# Fyre-BASIC-BOTtom.net
KiCad netlist of a schematic drawn in EAGLE
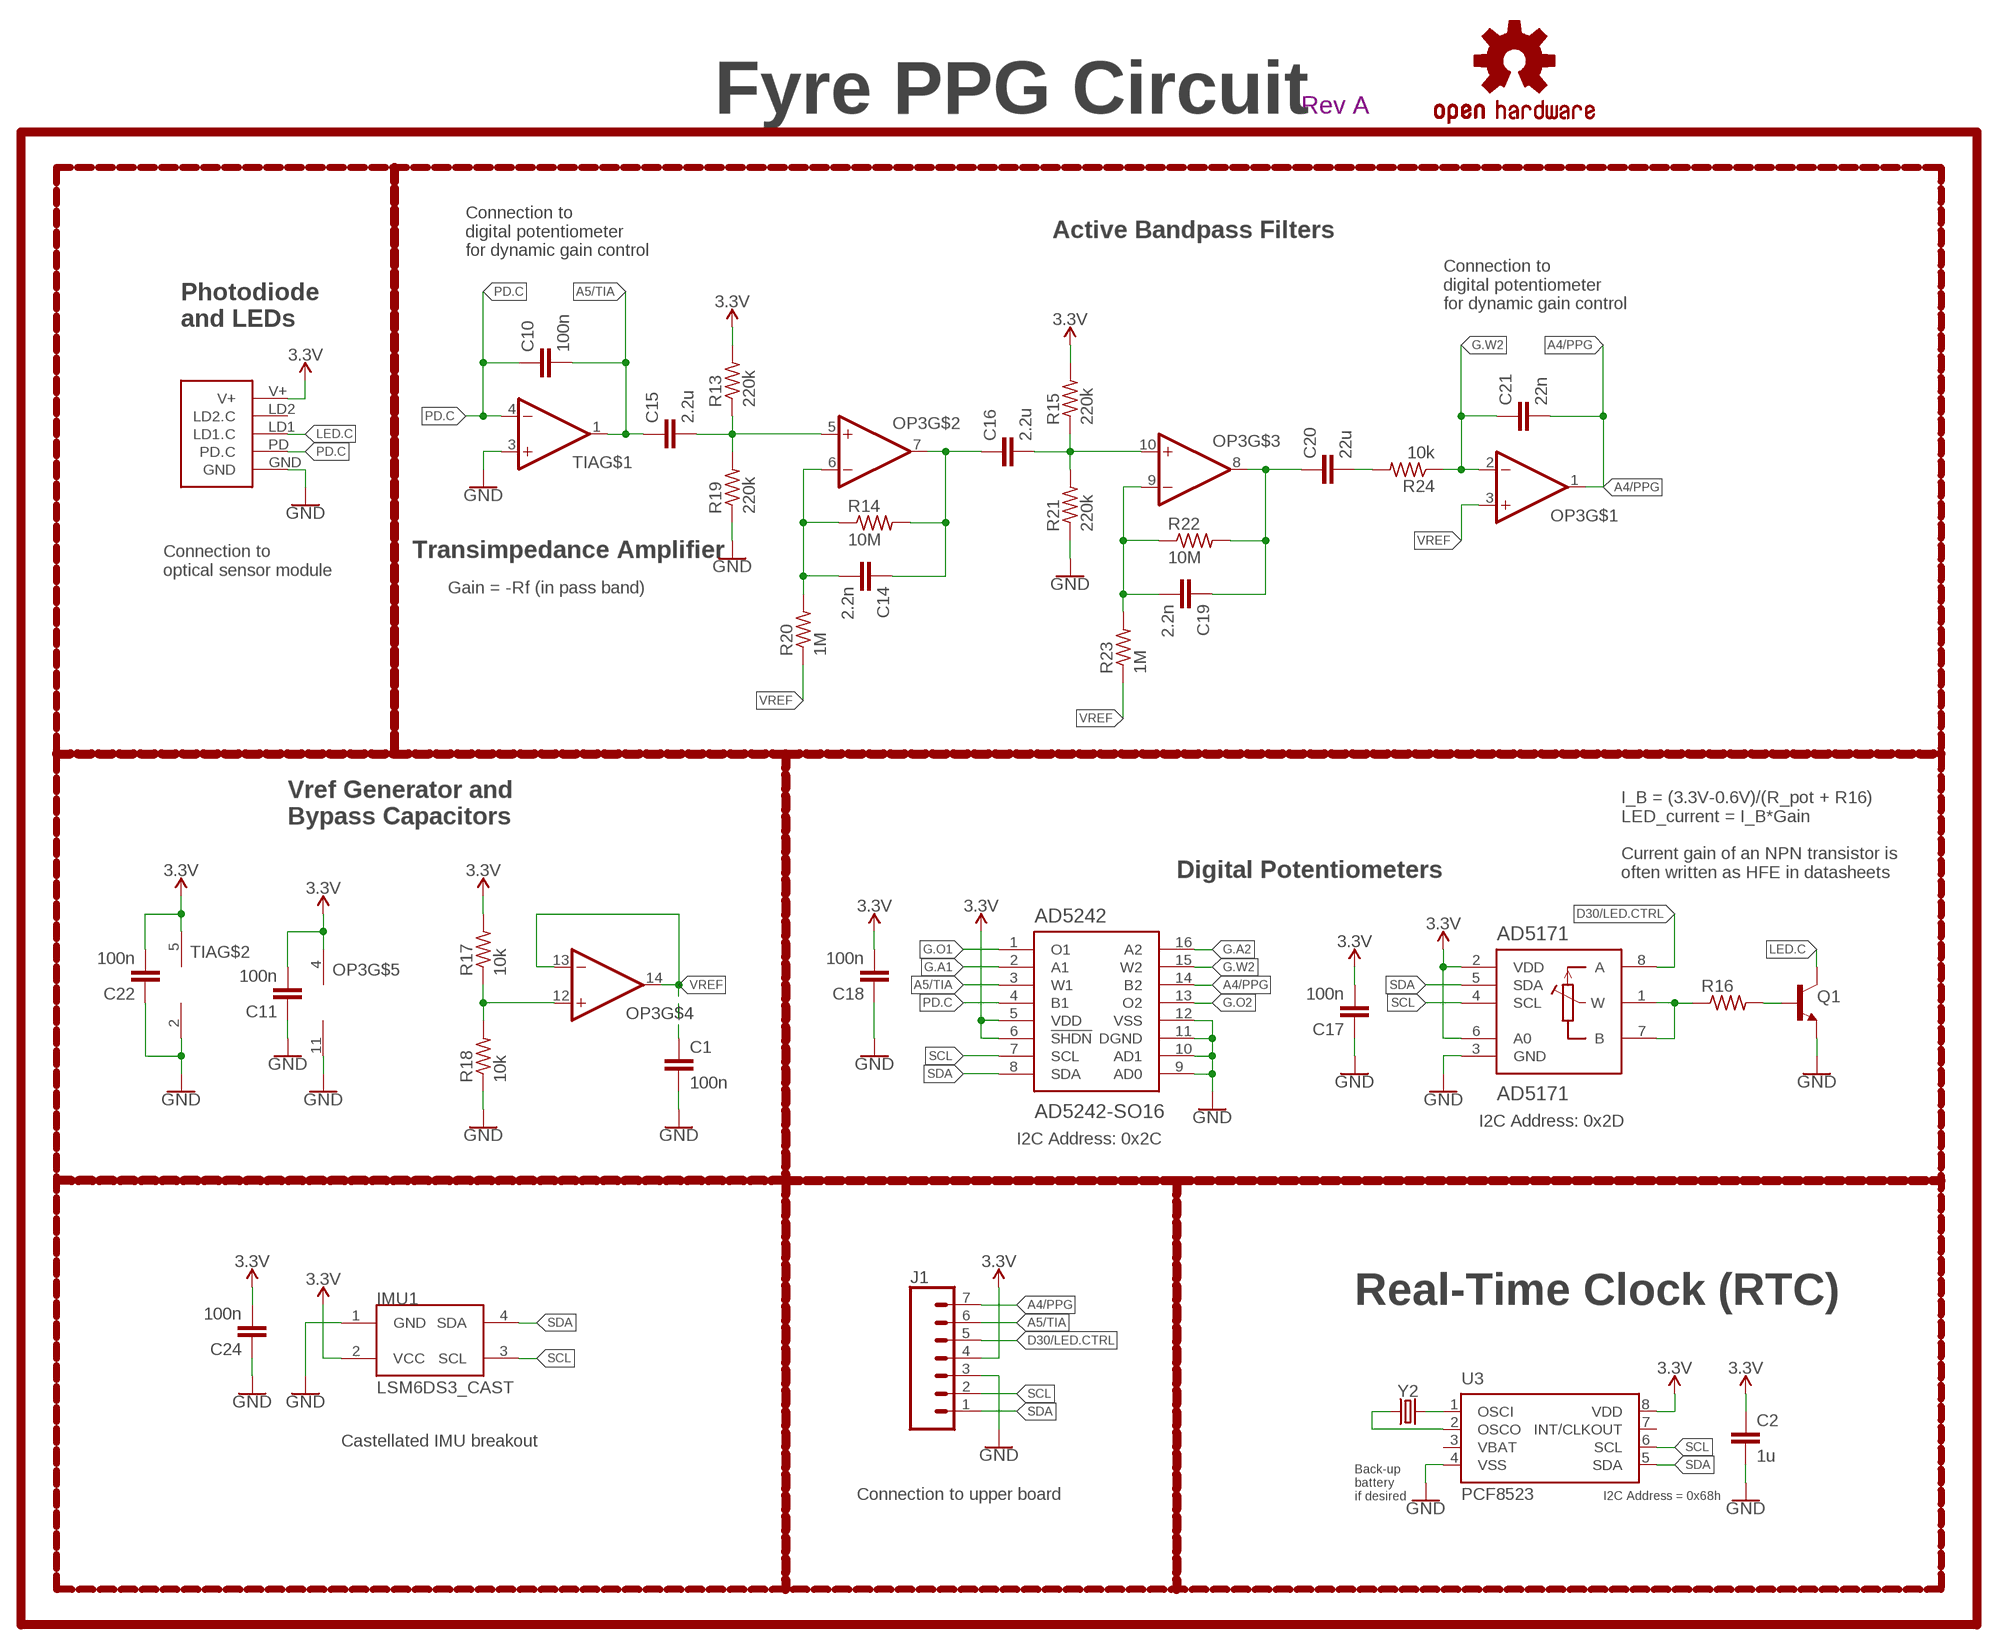
[diagram p0: schematic, sheet 1]

(export (version "E")
  (design (tool "Eeschema 10.0.6"))
  (components
    (comp (ref "AD5171")
      (value "AD5171")
      (footprint "eagle-import:SOT-23-8")
      (libsource (lib "eagle-import") (part "AD5171"))
    )
    (comp (ref "AD5242")
      (value "AD5242-SO16")
      (footprint "eagle-import:SO16")
      (libsource (lib "eagle-import") (part "AD5242-SO16"))
    )
    (comp (ref "C1")
      (value "100n")
      (footprint "eagle-import:C0603")
      (libsource (lib "eagle-import") (part "CAPACITOR0603"))
    )
    (comp (ref "C2")
      (value "1u")
      (footprint "eagle-import:C0603")
      (libsource (lib "eagle-import") (part "CAPACITOR0603"))
    )
    (comp (ref "C10")
      (value "100n")
      (footprint "eagle-import:C0603")
      (libsource (lib "eagle-import") (part "CAPACITOR0603"))
    )
    (comp (ref "C11")
      (value "100n")
      (footprint "eagle-import:C0603")
      (libsource (lib "eagle-import") (part "CAPACITOR0603"))
    )
    (comp (ref "C14")
      (value "2.2n")
      (footprint "eagle-import:C0603")
      (libsource (lib "eagle-import") (part "CAPACITOR0603"))
    )
    (comp (ref "C15")
      (value "2.2u")
      (footprint "eagle-import:C0603")
      (libsource (lib "eagle-import") (part "CAPACITOR0603"))
    )
    (comp (ref "C16")
      (value "2.2u")
      (footprint "eagle-import:C0603")
      (libsource (lib "eagle-import") (part "CAPACITOR0603"))
    )
    (comp (ref "C17")
      (value "100n")
      (footprint "eagle-import:C0603")
      (libsource (lib "eagle-import") (part "CAPACITOR0603"))
    )
    (comp (ref "C18")
      (value "100n")
      (footprint "eagle-import:C0603")
      (libsource (lib "eagle-import") (part "CAPACITOR0603"))
    )
    (comp (ref "C19")
      (value "2.2n")
      (footprint "eagle-import:C0603")
      (libsource (lib "eagle-import") (part "CAPACITOR0603"))
    )
    (comp (ref "C20")
      (value "22u")
      (footprint "eagle-import:C0603")
      (libsource (lib "eagle-import") (part "CAPACITOR0603"))
    )
    (comp (ref "C21")
      (value "22n")
      (footprint "eagle-import:C0603")
      (libsource (lib "eagle-import") (part "CAPACITOR0603"))
    )
    (comp (ref "C22")
      (value "100n")
      (footprint "eagle-import:C0603")
      (libsource (lib "eagle-import") (part "CAPACITOR0603"))
    )
    (comp (ref "C24")
      (value "100n")
      (footprint "eagle-import:C0603")
      (libsource (lib "eagle-import") (part "CAPACITOR0603"))
    )
    (comp (ref "IMU1")
      (value "LSM6DS3_CAST")
      (footprint "eagle-import:LSM6DS3_CAST")
      (libsource (lib "eagle-import") (part "LSM6DS3_CAST"))
    )
    (comp (ref "J1")
      (value "CONN_07-1.27MM")
      (footprint "eagle-import:1X07_1.27MM")
      (libsource (lib "eagle-import") (part "CONN_07-1.27MM"))
    )
    (comp (ref "LOGO1")
      (value "REVISION.A")
      (footprint "eagle-import:REV.A")
      (libsource (lib "eagle-import") (part "REVISION.A"))
    )
    (comp (ref "LOGO2")
      (value "OSHW-LOGOS")
      (footprint "eagle-import:OSHW-LOGO-S")
      (libsource (lib "eagle-import") (part "OSHW-LOGOS"))
    )
    (comp (ref "OP3")
      (value "OP-QUAD-SO14")
      (footprint "eagle-import:SO14")
      (libsource (lib "eagle-import") (part "OP-QUAD-SO14"))
    )
    (comp (ref "Q1")
      (value "NPN-GENERIC")
      (footprint "eagle-import:SOT23-3")
      (libsource (lib "eagle-import") (part "NPN-GENERIC"))
    )
    (comp (ref "R13")
      (value "220k")
      (footprint "eagle-import:R0603")
      (libsource (lib "eagle-import") (part "RESISTOR0603"))
    )
    (comp (ref "R14")
      (value "10M")
      (footprint "eagle-import:R0603")
      (libsource (lib "eagle-import") (part "RESISTOR0603"))
    )
    (comp (ref "R15")
      (value "220k")
      (footprint "eagle-import:R0603")
      (libsource (lib "eagle-import") (part "RESISTOR0603"))
    )
    (comp (ref "R16")
      (value "RESISTOR0603")
      (footprint "eagle-import:R0603")
      (libsource (lib "eagle-import") (part "RESISTOR0603"))
    )
    (comp (ref "R17")
      (value "10k")
      (footprint "eagle-import:R0402")
      (libsource (lib "eagle-import") (part "RESISTOR0402"))
    )
    (comp (ref "R18")
      (value "10k")
      (footprint "eagle-import:R0402")
      (libsource (lib "eagle-import") (part "RESISTOR0402"))
    )
    (comp (ref "R19")
      (value "220k")
      (footprint "eagle-import:R0603")
      (libsource (lib "eagle-import") (part "RESISTOR0603"))
    )
    (comp (ref "R20")
      (value "1M")
      (footprint "eagle-import:R0603")
      (libsource (lib "eagle-import") (part "RESISTOR0603"))
    )
    (comp (ref "R21")
      (value "220k")
      (footprint "eagle-import:R0603")
      (libsource (lib "eagle-import") (part "RESISTOR0603"))
    )
    (comp (ref "R22")
      (value "10M")
      (footprint "eagle-import:R0603")
      (libsource (lib "eagle-import") (part "RESISTOR0603"))
    )
    (comp (ref "R23")
      (value "1M")
      (footprint "eagle-import:R0603")
      (libsource (lib "eagle-import") (part "RESISTOR0603"))
    )
    (comp (ref "R24")
      (value "10k")
      (footprint "eagle-import:R0603")
      (libsource (lib "eagle-import") (part "RESISTOR0603"))
    )
    (comp (ref "TIA")
      (value "OP-SINGLEOT")
      (footprint "eagle-import:SOT23-5")
      (libsource (lib "eagle-import") (part "OP-SINGLEOT"))
    )
    (comp (ref "U$3")
      (value "PPG.MODULE.2")
      (footprint "eagle-import:PPG.MODULE.2")
      (libsource (lib "eagle-import") (part "PPG.MODULE.2"))
    )
    (comp (ref "U3")
      (value "PCF8523")
      (footprint "eagle-import:SO8")
      (fields
        (field (name "DIGIKEY") "568-5306-1-ND")
        (field (name "I2C_ADDRESS") "0x68h")
        (field (name "MFN") "PCF8523T/1,118")
        (field (name "MFN_MANUFACTURER") "NXP USA Inc.")
      )
      (libsource (lib "eagle-import") (part "PCF8523"))
    )
    (comp (ref "Y2")
      (value "32.7680kHz")
      (footprint "eagle-import:2-SMD.NOLEAD.2.0MMTO1.2MM")
      (fields (field (name "FREQ") "32.7680KHZ"))
      (libsource (lib "eagle-import") (part "CRYSTALECS-.327-12.5-12-C-TR"))
    )
  )
  (nets
    (net (code "1") (name "/VBAT") (class "Default")
      (node (ref "U3") (pin "3") (pinfunction "VBAT_3") (pintype "power_in"))
    )
    (net (code "2") (name "3.3V") (class "Default")
      (node (ref "AD5171") (pin "2") (pinfunction "VDD_2") (pintype "bidirectional"))
      (node (ref "AD5171") (pin "6") (pinfunction "A0_6") (pintype "bidirectional"))
      (node (ref "AD5242") (pin "5") (pinfunction "VDD_5") (pintype "bidirectional"))
      (node (ref "AD5242") (pin "6") (pinfunction "~{SHDN}_6") (pintype "bidirectional"))
      (node (ref "C11") (pin "2") (pinfunction "2_2") (pintype "passive"))
      (node (ref "C17") (pin "2") (pinfunction "2_2") (pintype "passive"))
      (node (ref "C18") (pin "2") (pinfunction "2_2") (pintype "passive"))
      (node (ref "C2") (pin "1") (pinfunction "1_1") (pintype "passive"))
      (node (ref "C22") (pin "2") (pinfunction "2_2") (pintype "passive"))
      (node (ref "C24") (pin "2") (pinfunction "2_2") (pintype "passive"))
      (node (ref "IMU1") (pin "2") (pinfunction "VCC_2") (pintype "bidirectional"))
      (node (ref "J1") (pin "4") (pinfunction "4_4") (pintype "passive"))
      (node (ref "OP3") (pin "4") (pinfunction "V+_4") (pintype "power_in"))
      (node (ref "R13") (pin "2") (pinfunction "2_2") (pintype "passive"))
      (node (ref "R15") (pin "2") (pinfunction "2_2") (pintype "passive"))
      (node (ref "R17") (pin "2") (pinfunction "2_2") (pintype "passive"))
      (node (ref "TIA") (pin "5") (pinfunction "V+_5") (pintype "power_in"))
      (node (ref "U$3") (pin "V+") (pinfunction "V+_V+") (pintype "bidirectional"))
      (node (ref "U3") (pin "8") (pinfunction "VDD_8") (pintype "power_in"))
    )
    (net (code "3") (name "A4{slash}PPG") (class "Default")
      (node (ref "AD5242") (pin "14") (pinfunction "B2_14") (pintype "bidirectional"))
      (node (ref "C21") (pin "2") (pinfunction "2_2") (pintype "passive"))
      (node (ref "J1") (pin "7") (pinfunction "7_7") (pintype "passive"))
      (node (ref "OP3") (pin "1") (pinfunction "OUT_1") (pintype "output"))
    )
    (net (code "4") (name "A5{slash}TIA") (class "Default")
      (node (ref "AD5242") (pin "3") (pinfunction "W1_3") (pintype "bidirectional"))
      (node (ref "C10") (pin "2") (pinfunction "2_2") (pintype "passive"))
      (node (ref "C15") (pin "1") (pinfunction "1_1") (pintype "passive"))
      (node (ref "J1") (pin "6") (pinfunction "6_6") (pintype "passive"))
      (node (ref "TIA") (pin "1") (pinfunction "OUT_1") (pintype "output"))
    )
    (net (code "5") (name "D30{slash}LED.CTRL") (class "Default")
      (node (ref "AD5171") (pin "8") (pinfunction "A_8") (pintype "bidirectional"))
      (node (ref "J1") (pin "5") (pinfunction "5_5") (pintype "passive"))
    )
    (net (code "6") (name "G.A1") (class "Default")
      (node (ref "AD5242") (pin "2") (pinfunction "A1_2") (pintype "bidirectional"))
    )
    (net (code "7") (name "G.A2") (class "Default")
      (node (ref "AD5242") (pin "16") (pinfunction "A2_16") (pintype "bidirectional"))
    )
    (net (code "8") (name "G.O1") (class "Default")
      (node (ref "AD5242") (pin "1") (pinfunction "O1_1") (pintype "bidirectional"))
    )
    (net (code "9") (name "G.O2") (class "Default")
      (node (ref "AD5242") (pin "13") (pinfunction "O2_13") (pintype "bidirectional"))
    )
    (net (code "10") (name "G.W2") (class "Default")
      (node (ref "AD5242") (pin "15") (pinfunction "W2_15") (pintype "bidirectional"))
      (node (ref "C21") (pin "1") (pinfunction "1_1") (pintype "passive"))
      (node (ref "OP3") (pin "2") (pinfunction "-IN_2") (pintype "input"))
      (node (ref "R24") (pin "1") (pinfunction "1_1") (pintype "passive"))
    )
    (net (code "11") (name "GND") (class "Default")
      (node (ref "AD5171") (pin "3") (pinfunction "GND_3") (pintype "bidirectional"))
      (node (ref "AD5242") (pin "10") (pinfunction "AD1_10") (pintype "bidirectional"))
      (node (ref "AD5242") (pin "11") (pinfunction "DGND_11") (pintype "bidirectional"))
      (node (ref "AD5242") (pin "12") (pinfunction "VSS_12") (pintype "bidirectional"))
      (node (ref "AD5242") (pin "9") (pinfunction "AD0_9") (pintype "bidirectional"))
      (node (ref "C1") (pin "2") (pinfunction "2_2") (pintype "passive"))
      (node (ref "C11") (pin "1") (pinfunction "1_1") (pintype "passive"))
      (node (ref "C17") (pin "1") (pinfunction "1_1") (pintype "passive"))
      (node (ref "C18") (pin "1") (pinfunction "1_1") (pintype "passive"))
      (node (ref "C2") (pin "2") (pinfunction "2_2") (pintype "passive"))
      (node (ref "C22") (pin "1") (pinfunction "1_1") (pintype "passive"))
      (node (ref "C24") (pin "1") (pinfunction "1_1") (pintype "passive"))
      (node (ref "IMU1") (pin "1") (pinfunction "GND_1") (pintype "bidirectional"))
      (node (ref "J1") (pin "3") (pinfunction "3_3") (pintype "passive"))
      (node (ref "OP3") (pin "11") (pinfunction "V-_11") (pintype "power_in"))
      (node (ref "Q1") (pin "2") (pinfunction "E_2") (pintype "passive"))
      (node (ref "R18") (pin "1") (pinfunction "1_1") (pintype "passive"))
      (node (ref "R19") (pin "1") (pinfunction "1_1") (pintype "passive"))
      (node (ref "R21") (pin "1") (pinfunction "1_1") (pintype "passive"))
      (node (ref "TIA") (pin "2") (pinfunction "V-_2") (pintype "power_in"))
      (node (ref "TIA") (pin "3") (pinfunction "+IN_3") (pintype "input"))
      (node (ref "U$3") (pin "GND") (pinfunction "GND_GND") (pintype "bidirectional"))
      (node (ref "U3") (pin "4") (pinfunction "VSS_4") (pintype "power_in"))
    )
    (net (code "12") (name "LED.C") (class "Default")
      (node (ref "Q1") (pin "3") (pinfunction "C_3") (pintype "passive"))
      (node (ref "U$3") (pin "LD1") (pinfunction "LD1.C_LD1") (pintype "bidirectional"))
    )
    (net (code "13") (name "Net-(AD5171-B)") (class "Default")
      (node (ref "AD5171") (pin "1") (pinfunction "W_1") (pintype "bidirectional"))
      (node (ref "AD5171") (pin "7") (pinfunction "B_7") (pintype "bidirectional"))
      (node (ref "R16") (pin "1") (pinfunction "1_1") (pintype "passive"))
    )
    (net (code "14") (name "Net-(C20-Pad2)") (class "Default")
      (node (ref "C20") (pin "2") (pinfunction "2_2") (pintype "passive"))
      (node (ref "R24") (pin "2") (pinfunction "2_2") (pintype "passive"))
    )
    (net (code "15") (name "Net-(OP3B-+IN)") (class "Default")
      (node (ref "C15") (pin "2") (pinfunction "2_2") (pintype "passive"))
      (node (ref "OP3") (pin "5") (pinfunction "+IN_5") (pintype "input"))
      (node (ref "R13") (pin "1") (pinfunction "1_1") (pintype "passive"))
      (node (ref "R19") (pin "2") (pinfunction "2_2") (pintype "passive"))
    )
    (net (code "16") (name "Net-(OP3B--IN)") (class "Default")
      (node (ref "C14") (pin "2") (pinfunction "2_2") (pintype "passive"))
      (node (ref "OP3") (pin "6") (pinfunction "-IN_6") (pintype "input"))
      (node (ref "R14") (pin "1") (pinfunction "1_1") (pintype "passive"))
      (node (ref "R20") (pin "2") (pinfunction "2_2") (pintype "passive"))
    )
    (net (code "17") (name "Net-(OP3B-OUT)") (class "Default")
      (node (ref "C14") (pin "1") (pinfunction "1_1") (pintype "passive"))
      (node (ref "C16") (pin "1") (pinfunction "1_1") (pintype "passive"))
      (node (ref "OP3") (pin "7") (pinfunction "OUT_7") (pintype "output"))
      (node (ref "R14") (pin "2") (pinfunction "2_2") (pintype "passive"))
    )
    (net (code "18") (name "Net-(OP3C-+IN)") (class "Default")
      (node (ref "C16") (pin "2") (pinfunction "2_2") (pintype "passive"))
      (node (ref "OP3") (pin "10") (pinfunction "+IN_10") (pintype "input"))
      (node (ref "R15") (pin "1") (pinfunction "1_1") (pintype "passive"))
      (node (ref "R21") (pin "2") (pinfunction "2_2") (pintype "passive"))
    )
    (net (code "19") (name "Net-(OP3C--IN)") (class "Default")
      (node (ref "C19") (pin "2") (pinfunction "2_2") (pintype "passive"))
      (node (ref "OP3") (pin "9") (pinfunction "-IN_9") (pintype "input"))
      (node (ref "R22") (pin "1") (pinfunction "1_1") (pintype "passive"))
      (node (ref "R23") (pin "2") (pinfunction "2_2") (pintype "passive"))
    )
    (net (code "20") (name "Net-(OP3C-OUT)") (class "Default")
      (node (ref "C19") (pin "1") (pinfunction "1_1") (pintype "passive"))
      (node (ref "C20") (pin "1") (pinfunction "1_1") (pintype "passive"))
      (node (ref "OP3") (pin "8") (pinfunction "OUT_8") (pintype "output"))
      (node (ref "R22") (pin "2") (pinfunction "2_2") (pintype "passive"))
    )
    (net (code "21") (name "Net-(OP3D-+IN)") (class "Default")
      (node (ref "OP3") (pin "12") (pinfunction "+IN_12") (pintype "input"))
      (node (ref "R17") (pin "1") (pinfunction "1_1") (pintype "passive"))
      (node (ref "R18") (pin "2") (pinfunction "2_2") (pintype "passive"))
    )
    (net (code "22") (name "Net-(Q1-B)") (class "Default")
      (node (ref "Q1") (pin "1") (pinfunction "B_1") (pintype "passive"))
      (node (ref "R16") (pin "2") (pinfunction "2_2") (pintype "passive"))
    )
    (net (code "23") (name "Net-(U3-OSCI)") (class "Default")
      (node (ref "U3") (pin "1") (pinfunction "OSCI_1") (pintype "bidirectional"))
      (node (ref "Y2") (pin "P$2") (pinfunction "2_P$2") (pintype "passive"))
    )
    (net (code "24") (name "Net-(U3-OSCO)") (class "Default")
      (node (ref "U3") (pin "2") (pinfunction "OSCO_2") (pintype "bidirectional"))
      (node (ref "Y2") (pin "P$1") (pinfunction "1_P$1") (pintype "passive"))
    )
    (net (code "25") (name "PD.C") (class "Default")
      (node (ref "AD5242") (pin "4") (pinfunction "B1_4") (pintype "bidirectional"))
      (node (ref "C10") (pin "1") (pinfunction "1_1") (pintype "passive"))
      (node (ref "TIA") (pin "4") (pinfunction "-IN_4") (pintype "input"))
      (node (ref "U$3") (pin "PD") (pinfunction "PD.C_PD") (pintype "bidirectional"))
    )
    (net (code "26") (name "SCL") (class "Default")
      (node (ref "AD5171") (pin "4") (pinfunction "SCL_4") (pintype "bidirectional"))
      (node (ref "AD5242") (pin "7") (pinfunction "SCL_7") (pintype "bidirectional"))
      (node (ref "IMU1") (pin "3") (pinfunction "SCL_3") (pintype "bidirectional"))
      (node (ref "J1") (pin "2") (pinfunction "2_2") (pintype "passive"))
      (node (ref "U3") (pin "6") (pinfunction "SCL_6") (pintype "bidirectional"))
    )
    (net (code "27") (name "SDA") (class "Default")
      (node (ref "AD5171") (pin "5") (pinfunction "SDA_5") (pintype "bidirectional"))
      (node (ref "AD5242") (pin "8") (pinfunction "SDA_8") (pintype "bidirectional"))
      (node (ref "IMU1") (pin "4") (pinfunction "SDA_4") (pintype "bidirectional"))
      (node (ref "J1") (pin "1") (pinfunction "1_1") (pintype "passive"))
      (node (ref "U3") (pin "5") (pinfunction "SDA_5") (pintype "bidirectional"))
    )
    (net (code "28") (name "VREF") (class "Default")
      (node (ref "C1") (pin "1") (pinfunction "1_1") (pintype "passive"))
      (node (ref "OP3") (pin "13") (pinfunction "-IN_13") (pintype "input"))
      (node (ref "OP3") (pin "14") (pinfunction "OUT_14") (pintype "output"))
      (node (ref "OP3") (pin "3") (pinfunction "+IN_3") (pintype "input"))
      (node (ref "R20") (pin "1") (pinfunction "1_1") (pintype "passive"))
      (node (ref "R23") (pin "1") (pinfunction "1_1") (pintype "passive"))
    )
    (net (code "29") (name "unconnected-(U$3-LD2.C-PadLD2)") (class "Default")
      (node (ref "U$3") (pin "LD2") (pinfunction "LD2.C_LD2") (pintype "bidirectional"))
    )
    (net (code "30") (name "unconnected-(U3-INT{slash}CLKOUT-Pad7)") (class "Default")
      (node (ref "U3") (pin "7") (pinfunction "INT/CLKOUT_7") (pintype "bidirectional"))
    )
  )
)
